# ECUEXT1_23.net
KiCad netlist of a schematic drawn in Altium Designer
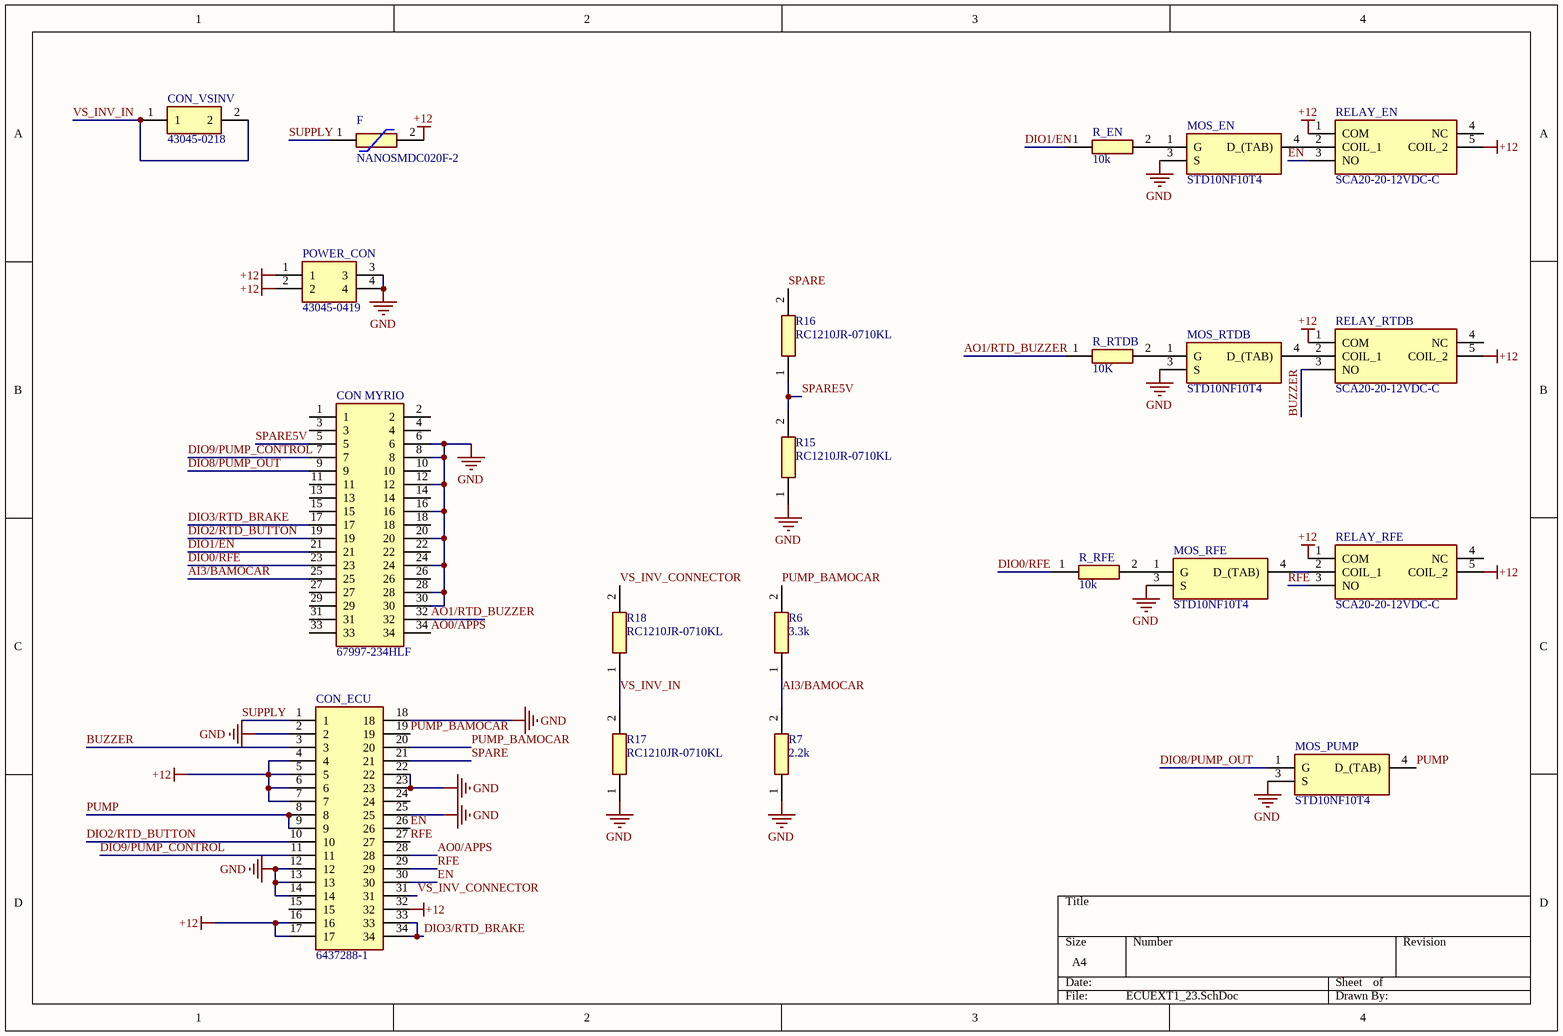
[diagram p0: ECUEXT1_23.SchDoc]

(export (version "E")
  (design (tool "Eeschema 10.0.6"))
  (components
    (comp (ref "CON MYRIO")
      (value "67997-234HLF")
      (footprint "SamacSys:HDRV34W67P254_2X17_4318X483X858P")
      (description "Connector")
      (fields (field (name "MOUSER PART NUMBER") "649-67997-234HLF"))
      (libsource (lib "*") (part "67997-234HLF"))
    )
    (comp (ref "CON_ECU")
      (value "6437288-1")
      (footprint "SamacSys:6437288-1")
      (description "Connector")
      (fields (field (name "MOUSER PART NUMBER") "571-6437288-1"))
      (libsource (lib "SamacSys") (part "6437288-1"))
    )
    (comp (ref "CON_VSINV")
      (value "43045-0218")
      (footprint "SamacSys:43045-02YY_181920")
      (description "Connector")
      (fields (field (name "MOUSER PART NUMBER") "538-43045-0218"))
      (libsource (lib "SamacSys") (part "43045-0218"))
    )
    (comp (ref "F")
      (value "NANOSMDC020F-2")
      (footprint "SamacSys:NANOSMDC016F2")
      (description "Resettable Fuse")
      (fields (field (name "MOUSER PART NUMBER") "650-NANOSMDC020F-2"))
      (libsource (lib "*") (part "NANOSMDC020F-2"))
    )
    (comp (ref "MOS_EN")
      (value "STD10NF10T4")
      (footprint "SamacSys:TO228P972X240-3N")
      (description "Integrated Circuit")
      (fields (field (name "MOUSER PART NUMBER") "511-STD10NF10"))
      (libsource (lib "*") (part "STD10NF10T4"))
    )
    (comp (ref "MOS_PUMP")
      (value "STD10NF10T4")
      (footprint "SamacSys:TO228P972X240-3N")
      (description "Integrated Circuit")
      (fields (field (name "MOUSER PART NUMBER") "511-STD10NF10"))
      (libsource (lib "*") (part "STD10NF10T4"))
    )
    (comp (ref "MOS_RFE")
      (value "STD10NF10T4")
      (footprint "SamacSys:TO228P972X240-3N")
      (description "Integrated Circuit")
      (fields (field (name "MOUSER PART NUMBER") "511-STD10NF10"))
      (libsource (lib "*") (part "STD10NF10T4"))
    )
    (comp (ref "MOS_RTDB")
      (value "STD10NF10T4")
      (footprint "SamacSys:TO228P972X240-3N")
      (description "Integrated Circuit")
      (fields (field (name "MOUSER PART NUMBER") "511-STD10NF10"))
      (libsource (lib "*") (part "STD10NF10T4"))
    )
    (comp (ref "POWER_CON")
      (value "43045-0419")
      (footprint "SamacSys:43045-04YY_181920")
      (description "Connector")
      (fields (field (name "MOUSER PART NUMBER") "538-43045-0419"))
      (libsource (lib "SamacSys") (part "43045-0419"))
    )
    (comp (ref "R6")
      (value "3.3k")
      (footprint "SamacSys:RESC3126X60N")
      (description "Resistor")
      (fields
        (field (name "MANUFACTURER_PART_NUMBER") "RC1210JR-0710KL")
        (field (name "MOUSER PART NUMBER") "603-RC1210JR-0710KL")
      )
      (libsource (lib "") (part "RC1210JR-0710KL_1"))
    )
    (comp (ref "R7")
      (value "2.2k")
      (footprint "SamacSys:RESC3126X60N")
      (description "Resistor")
      (fields
        (field (name "MANUFACTURER_PART_NUMBER") "RC1210JR-0710KL")
        (field (name "MOUSER PART NUMBER") "603-RC1210JR-0710KL")
      )
      (libsource (lib "") (part "RC1210JR-0710KL_1"))
    )
    (comp (ref "R15")
      (value "RC1210JR-0710KL")
      (footprint "SamacSys:RESC3126X60N")
      (description "Resistor")
      (fields (field (name "MOUSER PART NUMBER") "603-RC1210JR-0710KL"))
      (libsource (lib "") (part "RC1210JR-0710KL_1"))
    )
    (comp (ref "R16")
      (value "RC1210JR-0710KL")
      (footprint "SamacSys:RESC3126X60N")
      (description "Resistor")
      (fields (field (name "MOUSER PART NUMBER") "603-RC1210JR-0710KL"))
      (libsource (lib "") (part "RC1210JR-0710KL_1"))
    )
    (comp (ref "R17")
      (value "RC1210JR-0710KL")
      (footprint "SamacSys:RESC3126X60N")
      (description "Resistor")
      (fields (field (name "MOUSER PART NUMBER") "603-RC1210JR-0710KL"))
      (libsource (lib "") (part "RC1210JR-0710KL_1"))
    )
    (comp (ref "R18")
      (value "RC1210JR-0710KL")
      (footprint "SamacSys:RESC3126X60N")
      (description "Resistor")
      (fields (field (name "MOUSER PART NUMBER") "603-RC1210JR-0710KL"))
      (libsource (lib "") (part "RC1210JR-0710KL_1"))
    )
    (comp (ref "RELAY_EN")
      (value "SCA20-20-12VDC-C")
      (footprint "SamacSys:SCA202012VDCC")
      (description "Relay or Contactor")
      (libsource (lib "SamacSys") (part "SCA20-20-12VDC-C"))
    )
    (comp (ref "RELAY_RFE")
      (value "SCA20-20-12VDC-C")
      (footprint "SamacSys:SCA202012VDCC")
      (description "Relay or Contactor")
      (libsource (lib "SamacSys") (part "SCA20-20-12VDC-C"))
    )
    (comp (ref "RELAY_RTDB")
      (value "SCA20-20-12VDC-C")
      (footprint "SamacSys:SCA202012VDCC")
      (description "Relay or Contactor")
      (libsource (lib "SamacSys") (part "SCA20-20-12VDC-C"))
    )
    (comp (ref "R_EN")
      (value "10k")
      (footprint "SamacSys:RESC3126X60N")
      (description "Resistor")
      (fields
        (field (name "MANUFACTURER_PART_NUMBER") "RC1210JR-0710KL")
        (field (name "MOUSER PART NUMBER") "603-RC1210JR-0710KL")
      )
      (libsource (lib "*") (part "RC1210JR-0710KL"))
    )
    (comp (ref "R_RFE")
      (value "10k")
      (footprint "SamacSys:RESC3126X60N")
      (description "Resistor")
      (fields
        (field (name "MANUFACTURER_PART_NUMBER") "RC1210JR-0710KL")
        (field (name "MOUSER PART NUMBER") "603-RC1210JR-0710KL")
      )
      (libsource (lib "*") (part "RC1210JR-0710KL"))
    )
    (comp (ref "R_RTDB")
      (value "10K")
      (footprint "SamacSys:RESC3126X60N")
      (description "Resistor")
      (fields
        (field (name "MANUFACTURER_PART_NUMBER") "RC1210JR-0710KL")
        (field (name "MOUSER PART NUMBER") "603-RC1210JR-0710KL")
      )
      (libsource (lib "SamacSys") (part "RC1210JR-0710KL"))
    )
  )
  (nets
    (net (code "1") (name "+12") (class "Default")
      (node (ref "CON_ECU") (pin "16") (pinfunction "16_16") (pintype "passive"))
      (node (ref "CON_ECU") (pin "17") (pinfunction "17_17") (pintype "passive"))
      (node (ref "CON_ECU") (pin "32") (pinfunction "32_32") (pintype "passive"))
      (node (ref "CON_ECU") (pin "4") (pinfunction "4_4") (pintype "passive"))
      (node (ref "CON_ECU") (pin "5") (pinfunction "5_5") (pintype "passive"))
      (node (ref "CON_ECU") (pin "6") (pinfunction "6_6") (pintype "passive"))
      (node (ref "CON_ECU") (pin "7") (pinfunction "7_7") (pintype "passive"))
      (node (ref "F") (pin "2") (pinfunction "2_2") (pintype "passive"))
      (node (ref "POWER_CON") (pin "1") (pinfunction "1_1") (pintype "passive"))
      (node (ref "POWER_CON") (pin "2") (pinfunction "2_2") (pintype "passive"))
      (node (ref "RELAY_EN") (pin "1") (pinfunction "COM_1") (pintype "passive"))
      (node (ref "RELAY_EN") (pin "5") (pinfunction "COIL_2_5") (pintype "passive"))
      (node (ref "RELAY_RFE") (pin "1") (pinfunction "COM_1") (pintype "passive"))
      (node (ref "RELAY_RFE") (pin "5") (pinfunction "COIL_2_5") (pintype "passive"))
      (node (ref "RELAY_RTDB") (pin "1") (pinfunction "COM_1") (pintype "passive"))
      (node (ref "RELAY_RTDB") (pin "5") (pinfunction "COIL_2_5") (pintype "passive"))
    )
    (net (code "2") (name "/AI3{slash}BAMOCAR") (class "Default")
      (node (ref "CON MYRIO") (pin "25") (pinfunction "25_25") (pintype "passive"))
      (node (ref "R6") (pin "1") (pinfunction "1_1") (pintype "passive"))
      (node (ref "R7") (pin "2") (pinfunction "2_2") (pintype "passive"))
    )
    (net (code "3") (name "/AO0{slash}APPS") (class "Default")
      (node (ref "CON MYRIO") (pin "34") (pinfunction "34_34") (pintype "passive"))
      (node (ref "CON_ECU") (pin "28") (pinfunction "28_28") (pintype "passive"))
    )
    (net (code "4") (name "/AO1{slash}RTD_BUZZER") (class "Default")
      (node (ref "CON MYRIO") (pin "32") (pinfunction "32_32") (pintype "passive"))
      (node (ref "R_RTDB") (pin "1") (pinfunction "1_1") (pintype "passive"))
    )
    (net (code "5") (name "/BUZZER") (class "Default")
      (node (ref "CON_ECU") (pin "3") (pinfunction "3_3") (pintype "passive"))
      (node (ref "RELAY_RTDB") (pin "3") (pinfunction "NO_3") (pintype "passive"))
    )
    (net (code "6") (name "/DIO0{slash}RFE") (class "Default")
      (node (ref "CON MYRIO") (pin "23") (pinfunction "23_23") (pintype "passive"))
      (node (ref "R_RFE") (pin "1") (pinfunction "1_1") (pintype "passive"))
    )
    (net (code "7") (name "/DIO1{slash}EN") (class "Default")
      (node (ref "CON MYRIO") (pin "21") (pinfunction "21_21") (pintype "passive"))
      (node (ref "R_EN") (pin "1") (pinfunction "1_1") (pintype "passive"))
    )
    (net (code "8") (name "/DIO2{slash}RTD_BUTTON") (class "Default")
      (node (ref "CON MYRIO") (pin "19") (pinfunction "19_19") (pintype "passive"))
      (node (ref "CON_ECU") (pin "10") (pinfunction "10_10") (pintype "passive"))
    )
    (net (code "9") (name "/DIO3{slash}RTD_BRAKE") (class "Default")
      (node (ref "CON MYRIO") (pin "17") (pinfunction "17_17") (pintype "passive"))
      (node (ref "CON_ECU") (pin "33") (pinfunction "33_33") (pintype "passive"))
      (node (ref "CON_ECU") (pin "34") (pinfunction "34_34") (pintype "passive"))
    )
    (net (code "10") (name "/DIO8{slash}PUMP_OUT") (class "Default")
      (node (ref "CON MYRIO") (pin "9") (pinfunction "9_9") (pintype "passive"))
      (node (ref "MOS_PUMP") (pin "1") (pinfunction "G_1") (pintype "passive"))
    )
    (net (code "11") (name "/DIO9{slash}PUMP_CONTROL") (class "Default")
      (node (ref "CON MYRIO") (pin "7") (pinfunction "7_7") (pintype "passive"))
      (node (ref "CON_ECU") (pin "11") (pinfunction "11_11") (pintype "passive"))
    )
    (net (code "12") (name "/EN") (class "Default")
      (node (ref "CON_ECU") (pin "26") (pinfunction "26_26") (pintype "passive"))
      (node (ref "CON_ECU") (pin "30") (pinfunction "30_30") (pintype "passive"))
      (node (ref "RELAY_EN") (pin "3") (pinfunction "NO_3") (pintype "passive"))
    )
    (net (code "13") (name "/PUMP") (class "Default")
      (node (ref "CON_ECU") (pin "8") (pinfunction "8_8") (pintype "passive"))
      (node (ref "CON_ECU") (pin "9") (pinfunction "9_9") (pintype "passive"))
      (node (ref "MOS_PUMP") (pin "4") (pinfunction "D_(TAB)_4") (pintype "passive"))
    )
    (net (code "14") (name "/PUMP_BAMOCAR") (class "Default")
      (node (ref "CON_ECU") (pin "19") (pinfunction "19_19") (pintype "passive"))
      (node (ref "CON_ECU") (pin "20") (pinfunction "20_20") (pintype "passive"))
      (node (ref "R6") (pin "2") (pinfunction "2_2") (pintype "passive"))
    )
    (net (code "15") (name "/RFE") (class "Default")
      (node (ref "CON_ECU") (pin "27") (pinfunction "27_27") (pintype "passive"))
      (node (ref "CON_ECU") (pin "29") (pinfunction "29_29") (pintype "passive"))
      (node (ref "RELAY_RFE") (pin "3") (pinfunction "NO_3") (pintype "passive"))
    )
    (net (code "16") (name "/SPARE") (class "Default")
      (node (ref "CON_ECU") (pin "21") (pinfunction "21_21") (pintype "passive"))
      (node (ref "R16") (pin "2") (pinfunction "2_2") (pintype "passive"))
    )
    (net (code "17") (name "/SPARE5V") (class "Default")
      (node (ref "CON MYRIO") (pin "5") (pinfunction "5_5") (pintype "passive"))
      (node (ref "R15") (pin "2") (pinfunction "2_2") (pintype "passive"))
      (node (ref "R16") (pin "1") (pinfunction "1_1") (pintype "passive"))
    )
    (net (code "18") (name "/SUPPLY") (class "Default")
      (node (ref "CON_ECU") (pin "1") (pinfunction "1_1") (pintype "passive"))
      (node (ref "F") (pin "1") (pinfunction "1_1") (pintype "passive"))
    )
    (net (code "19") (name "/VS_INV_CONNECTOR") (class "Default")
      (node (ref "CON_ECU") (pin "31") (pinfunction "31_31") (pintype "passive"))
      (node (ref "R18") (pin "2") (pinfunction "2_2") (pintype "passive"))
    )
    (net (code "20") (name "/VS_INV_IN") (class "Default")
      (node (ref "CON_VSINV") (pin "1") (pinfunction "1_1") (pintype "passive"))
      (node (ref "CON_VSINV") (pin "2") (pinfunction "2_2") (pintype "passive"))
      (node (ref "R17") (pin "2") (pinfunction "2_2") (pintype "passive"))
      (node (ref "R18") (pin "1") (pinfunction "1_1") (pintype "passive"))
    )
    (net (code "21") (name "GND") (class "Default")
      (node (ref "CON MYRIO") (pin "12") (pinfunction "12_12") (pintype "passive"))
      (node (ref "CON MYRIO") (pin "16") (pinfunction "16_16") (pintype "passive"))
      (node (ref "CON MYRIO") (pin "20") (pinfunction "20_20") (pintype "passive"))
      (node (ref "CON MYRIO") (pin "24") (pinfunction "24_24") (pintype "passive"))
      (node (ref "CON MYRIO") (pin "28") (pinfunction "28_28") (pintype "passive"))
      (node (ref "CON MYRIO") (pin "30") (pinfunction "30_30") (pintype "passive"))
      (node (ref "CON MYRIO") (pin "6") (pinfunction "6_6") (pintype "passive"))
      (node (ref "CON MYRIO") (pin "8") (pinfunction "8_8") (pintype "passive"))
      (node (ref "CON_ECU") (pin "12") (pinfunction "12_12") (pintype "passive"))
      (node (ref "CON_ECU") (pin "13") (pinfunction "13_13") (pintype "passive"))
      (node (ref "CON_ECU") (pin "14") (pinfunction "14_14") (pintype "passive"))
      (node (ref "CON_ECU") (pin "18") (pinfunction "18_18") (pintype "passive"))
      (node (ref "CON_ECU") (pin "2") (pinfunction "2_2") (pintype "passive"))
      (node (ref "CON_ECU") (pin "22") (pinfunction "22_22") (pintype "passive"))
      (node (ref "CON_ECU") (pin "23") (pinfunction "23_23") (pintype "passive"))
      (node (ref "CON_ECU") (pin "25") (pinfunction "25_25") (pintype "passive"))
      (node (ref "MOS_EN") (pin "3") (pinfunction "S_3") (pintype "passive"))
      (node (ref "MOS_PUMP") (pin "3") (pinfunction "S_3") (pintype "passive"))
      (node (ref "MOS_RFE") (pin "3") (pinfunction "S_3") (pintype "passive"))
      (node (ref "MOS_RTDB") (pin "3") (pinfunction "S_3") (pintype "passive"))
      (node (ref "POWER_CON") (pin "3") (pinfunction "3_3") (pintype "passive"))
      (node (ref "POWER_CON") (pin "4") (pinfunction "4_4") (pintype "passive"))
      (node (ref "R15") (pin "1") (pinfunction "1_1") (pintype "passive"))
      (node (ref "R17") (pin "1") (pinfunction "1_1") (pintype "passive"))
      (node (ref "R7") (pin "1") (pinfunction "1_1") (pintype "passive"))
    )
    (net (code "22") (name "Net-(MOS_EN-D_(TAB))") (class "Default")
      (node (ref "MOS_EN") (pin "4") (pinfunction "D_(TAB)_4") (pintype "passive"))
      (node (ref "RELAY_EN") (pin "2") (pinfunction "COIL_1_2") (pintype "passive"))
    )
    (net (code "23") (name "Net-(MOS_EN-G)") (class "Default")
      (node (ref "MOS_EN") (pin "1") (pinfunction "G_1") (pintype "passive"))
      (node (ref "R_EN") (pin "2") (pinfunction "2_2") (pintype "passive"))
    )
    (net (code "24") (name "Net-(MOS_RFE-D_(TAB))") (class "Default")
      (node (ref "MOS_RFE") (pin "4") (pinfunction "D_(TAB)_4") (pintype "passive"))
      (node (ref "RELAY_RFE") (pin "2") (pinfunction "COIL_1_2") (pintype "passive"))
    )
    (net (code "25") (name "Net-(MOS_RFE-G)") (class "Default")
      (node (ref "MOS_RFE") (pin "1") (pinfunction "G_1") (pintype "passive"))
      (node (ref "R_RFE") (pin "2") (pinfunction "2_2") (pintype "passive"))
    )
    (net (code "26") (name "Net-(MOS_RTDB-D_(TAB))") (class "Default")
      (node (ref "MOS_RTDB") (pin "4") (pinfunction "D_(TAB)_4") (pintype "passive"))
      (node (ref "RELAY_RTDB") (pin "2") (pinfunction "COIL_1_2") (pintype "passive"))
    )
    (net (code "27") (name "Net-(MOS_RTDB-G)") (class "Default")
      (node (ref "MOS_RTDB") (pin "1") (pinfunction "G_1") (pintype "passive"))
      (node (ref "R_RTDB") (pin "2") (pinfunction "2_2") (pintype "passive"))
    )
    (net (code "28") (name "unconnected-(CON MYRIO-Pad1)") (class "Default")
      (node (ref "CON MYRIO") (pin "1") (pinfunction "1_1") (pintype "passive"))
    )
    (net (code "29") (name "unconnected-(CON MYRIO-Pad2)") (class "Default")
      (node (ref "CON MYRIO") (pin "2") (pinfunction "2_2") (pintype "passive"))
    )
    (net (code "30") (name "unconnected-(CON MYRIO-Pad3)") (class "Default")
      (node (ref "CON MYRIO") (pin "3") (pinfunction "3_3") (pintype "passive"))
    )
    (net (code "31") (name "unconnected-(CON MYRIO-Pad4)") (class "Default")
      (node (ref "CON MYRIO") (pin "4") (pinfunction "4_4") (pintype "passive"))
    )
    (net (code "32") (name "unconnected-(CON MYRIO-Pad10)") (class "Default")
      (node (ref "CON MYRIO") (pin "10") (pinfunction "10_10") (pintype "passive"))
    )
    (net (code "33") (name "unconnected-(CON MYRIO-Pad11)") (class "Default")
      (node (ref "CON MYRIO") (pin "11") (pinfunction "11_11") (pintype "passive"))
    )
    (net (code "34") (name "unconnected-(CON MYRIO-Pad13)") (class "Default")
      (node (ref "CON MYRIO") (pin "13") (pinfunction "13_13") (pintype "passive"))
    )
    (net (code "35") (name "unconnected-(CON MYRIO-Pad14)") (class "Default")
      (node (ref "CON MYRIO") (pin "14") (pinfunction "14_14") (pintype "passive"))
    )
    (net (code "36") (name "unconnected-(CON MYRIO-Pad15)") (class "Default")
      (node (ref "CON MYRIO") (pin "15") (pinfunction "15_15") (pintype "passive"))
    )
    (net (code "37") (name "unconnected-(CON MYRIO-Pad18)") (class "Default")
      (node (ref "CON MYRIO") (pin "18") (pinfunction "18_18") (pintype "passive"))
    )
    (net (code "38") (name "unconnected-(CON MYRIO-Pad22)") (class "Default")
      (node (ref "CON MYRIO") (pin "22") (pinfunction "22_22") (pintype "passive"))
    )
    (net (code "39") (name "unconnected-(CON MYRIO-Pad26)") (class "Default")
      (node (ref "CON MYRIO") (pin "26") (pinfunction "26_26") (pintype "passive"))
    )
    (net (code "40") (name "unconnected-(CON MYRIO-Pad27)") (class "Default")
      (node (ref "CON MYRIO") (pin "27") (pinfunction "27_27") (pintype "passive"))
    )
    (net (code "41") (name "unconnected-(CON MYRIO-Pad29)") (class "Default")
      (node (ref "CON MYRIO") (pin "29") (pinfunction "29_29") (pintype "passive"))
    )
    (net (code "42") (name "unconnected-(CON MYRIO-Pad31)") (class "Default")
      (node (ref "CON MYRIO") (pin "31") (pinfunction "31_31") (pintype "passive"))
    )
    (net (code "43") (name "unconnected-(CON MYRIO-Pad33)") (class "Default")
      (node (ref "CON MYRIO") (pin "33") (pinfunction "33_33") (pintype "passive"))
    )
    (net (code "44") (name "unconnected-(CON_ECU-Pad15)") (class "Default")
      (node (ref "CON_ECU") (pin "15") (pinfunction "15_15") (pintype "passive"))
    )
    (net (code "45") (name "unconnected-(CON_ECU-Pad24)") (class "Default")
      (node (ref "CON_ECU") (pin "24") (pinfunction "24_24") (pintype "passive"))
    )
    (net (code "46") (name "unconnected-(RELAY_EN-NC-Pad4)") (class "Default")
      (node (ref "RELAY_EN") (pin "4") (pinfunction "NC_4") (pintype "passive"))
    )
    (net (code "47") (name "unconnected-(RELAY_RFE-NC-Pad4)") (class "Default")
      (node (ref "RELAY_RFE") (pin "4") (pinfunction "NC_4") (pintype "passive"))
    )
    (net (code "48") (name "unconnected-(RELAY_RTDB-NC-Pad4)") (class "Default")
      (node (ref "RELAY_RTDB") (pin "4") (pinfunction "NC_4") (pintype "passive"))
    )
  )
)
